# cc3d.net
KiCad netlist of a schematic drawn in Altium Designer
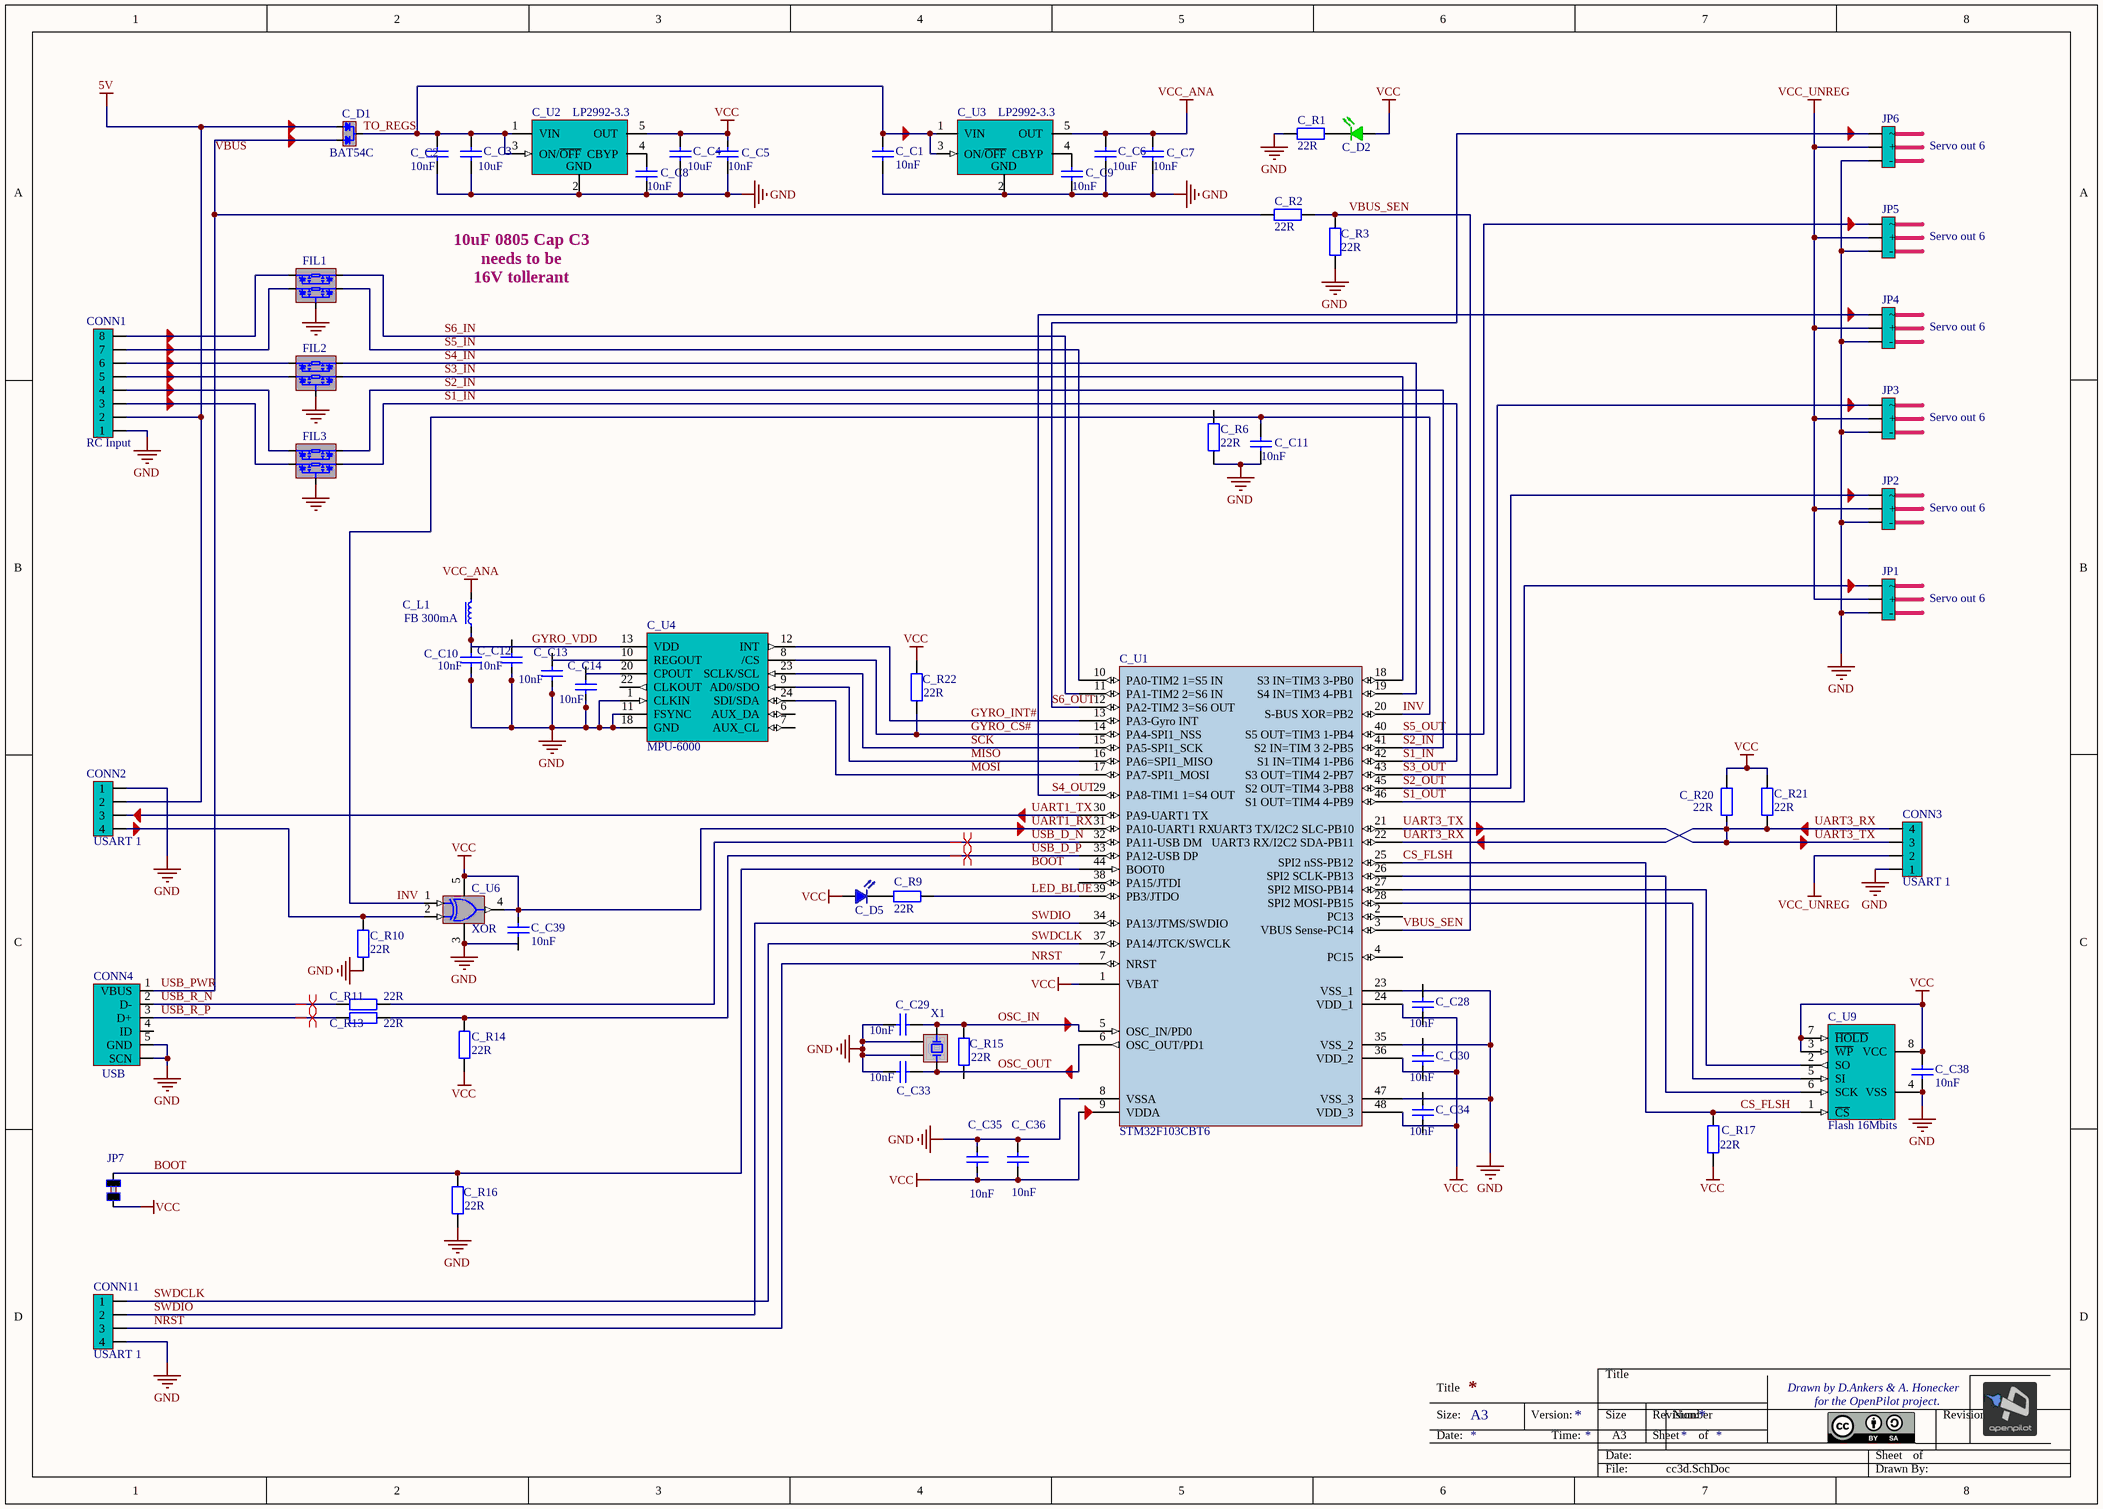
[diagram p0: cc3d.SchDoc]

(export (version "E")
  (design (tool "Eeschema 10.0.6"))
  (components
    (comp (ref "CONN1")
      (value "RC Input")
      (footprint "JST SH 8 Pin Side Entry")
      (description "JST-SH 8-pin Side Entry Socket")
      (fields (field (name "MANUFACTURER") "Generic Components"))
      (libsource (lib "CopterControl 3D") (part "JST-SH 8-pin Side Entry Socket"))
    )
    (comp (ref "CONN2")
      (value "USART 1")
      (footprint "JST SH 4 Pin Side Entry")
      (description "JST-SH 4-pin Side Entry Socket")
      (fields (field (name "MANUFACTURER") "Generic Components"))
      (libsource (lib "CopterControl 3D") (part "JST-SH 4-pin Side Entry Socket"))
    )
    (comp (ref "CONN3")
      (value "USART 1")
      (footprint "JST SH 4 Pin Side Entry")
      (description "JST-SH 4-pin Side Entry Socket")
      (fields (field (name "MANUFACTURER") "Generic Components"))
      (libsource (lib "") (part "JST-SH 4-pin Side Entry Socket_1"))
    )
    (comp (ref "CONN4")
      (value "USB")
      (footprint "USB SMD")
      (description "USB Type-B SMT Socket")
      (libsource (lib "CopterControl 3D") (part "USB_SMT_B"))
    )
    (comp (ref "CONN11")
      (value "USART 1")
      (footprint "JST SH 4 Pin Side Entry")
      (description "JST-SH 4-pin Side Entry Socket")
      (fields (field (name "MANUFACTURER") "Generic Components"))
      (libsource (lib "CopterControl 3D") (part "JST-SH 4-pin Side Entry Socket"))
    )
    (comp (ref "C_C1")
      (value "10nF")
      (footprint "CAP603N")
      (description "Capacitor SMD")
      (fields (field (name "Comment") "Cap603") (field (name "PUBLISHER") "The OpenPilot Project"))
      (libsource (lib "CopterControl 3D") (part "Cap603"))
    )
    (comp (ref "C_C2")
      (value "10nF")
      (footprint "CAP603L")
      (description "Capacitor SMD")
      (fields (field (name "Comment") "Cap603") (field (name "PUBLISHER") "The OpenPilot Project"))
      (libsource (lib "CopterControl 3D") (part "Cap603"))
    )
    (comp (ref "C_C3")
      (value "10uF")
      (footprint "CAP805L")
      (description "Capacitor SMD")
      (fields (field (name "Comment") "Cap805") (field (name "PUBLISHER") "The OpenPilot Project"))
      (libsource (lib "CopterControl 3D") (part "Cap805"))
    )
    (comp (ref "C_C4")
      (value "10uF")
      (footprint "CAP805L")
      (description "Capacitor SMD")
      (fields (field (name "Comment") "Cap805") (field (name "PUBLISHER") "The OpenPilot Project"))
      (libsource (lib "CopterControl 3D") (part "Cap805"))
    )
    (comp (ref "C_C5")
      (value "10nF")
      (footprint "CAP603N")
      (description "Capacitor SMD")
      (fields (field (name "Comment") "Cap603") (field (name "PUBLISHER") "The OpenPilot Project"))
      (libsource (lib "CopterControl 3D") (part "Cap603"))
    )
    (comp (ref "C_C6")
      (value "10uF")
      (footprint "CAP805L")
      (description "Capacitor SMD")
      (fields (field (name "Comment") "Cap805") (field (name "PUBLISHER") "The OpenPilot Project"))
      (libsource (lib "CopterControl 3D") (part "Cap805"))
    )
    (comp (ref "C_C7")
      (value "10nF")
      (footprint "CAP603N")
      (description "Capacitor SMD")
      (fields (field (name "Comment") "Cap603") (field (name "PUBLISHER") "The OpenPilot Project"))
      (libsource (lib "CopterControl 3D") (part "Cap603"))
    )
    (comp (ref "C_C8")
      (value "10nF")
      (footprint "CAP603N")
      (description "Capacitor SMD")
      (fields (field (name "Comment") "Cap603") (field (name "PUBLISHER") "The OpenPilot Project"))
      (libsource (lib "CopterControl 3D") (part "Cap603"))
    )
    (comp (ref "C_C9")
      (value "10nF")
      (footprint "CAP603N")
      (description "Capacitor SMD")
      (fields (field (name "Comment") "Cap603") (field (name "PUBLISHER") "The OpenPilot Project"))
      (libsource (lib "CopterControl 3D") (part "Cap603"))
    )
    (comp (ref "C_C10")
      (value "10nF")
      (footprint "CAP603L")
      (description "Capacitor SMD")
      (fields (field (name "Comment") "Cap603") (field (name "PUBLISHER") "The OpenPilot Project"))
      (libsource (lib "CopterControl 3D") (part "Cap603"))
    )
    (comp (ref "C_C11")
      (value "10nF")
      (footprint "CAP603N")
      (description "Capacitor SMD")
      (fields (field (name "Comment") "Cap603") (field (name "PUBLISHER") "The OpenPilot Project"))
      (libsource (lib "CopterControl 3D") (part "Cap603"))
    )
    (comp (ref "C_C12")
      (value "10nF")
      (footprint "CAP603L")
      (description "Capacitor SMD")
      (fields (field (name "Comment") "Cap603") (field (name "PUBLISHER") "The OpenPilot Project"))
      (libsource (lib "CopterControl 3D") (part "Cap603"))
    )
    (comp (ref "C_C13")
      (value "10nF")
      (footprint "CAP603L")
      (description "Capacitor SMD")
      (fields (field (name "Comment") "Cap603") (field (name "PUBLISHER") "The OpenPilot Project"))
      (libsource (lib "CopterControl 3D") (part "Cap603"))
    )
    (comp (ref "C_C14")
      (value "10nF")
      (footprint "CAP603L")
      (description "Capacitor SMD")
      (fields (field (name "Comment") "Cap603") (field (name "PUBLISHER") "The OpenPilot Project"))
      (libsource (lib "CopterControl 3D") (part "Cap603"))
    )
    (comp (ref "C_C28")
      (value "10nF")
      (footprint "CAP603N")
      (description "Capacitor SMD")
      (fields (field (name "Comment") "Cap603") (field (name "PUBLISHER") "The OpenPilot Project"))
      (libsource (lib "CopterControl 3D") (part "Cap603"))
    )
    (comp (ref "C_C29")
      (value "10nF")
      (footprint "CAP603N")
      (description "Capacitor SMD")
      (fields (field (name "Comment") "Cap603") (field (name "PUBLISHER") "The OpenPilot Project"))
      (libsource (lib "CopterControl 3D") (part "Cap603"))
    )
    (comp (ref "C_C30")
      (value "10nF")
      (footprint "CAP603N")
      (description "Capacitor SMD")
      (fields (field (name "Comment") "Cap603") (field (name "PUBLISHER") "The OpenPilot Project"))
      (libsource (lib "CopterControl 3D") (part "Cap603"))
    )
    (comp (ref "C_C33")
      (value "10nF")
      (footprint "CAP603N")
      (description "Capacitor SMD")
      (fields (field (name "Comment") "Cap603") (field (name "PUBLISHER") "The OpenPilot Project"))
      (libsource (lib "CopterControl 3D") (part "Cap603"))
    )
    (comp (ref "C_C34")
      (value "10nF")
      (footprint "CAP603N")
      (description "Capacitor SMD")
      (fields (field (name "Comment") "Cap603") (field (name "PUBLISHER") "The OpenPilot Project"))
      (libsource (lib "CopterControl 3D") (part "Cap603"))
    )
    (comp (ref "C_C35")
      (value "10nF")
      (footprint "CAP603L")
      (description "Capacitor SMD")
      (fields (field (name "Comment") "Cap603") (field (name "PUBLISHER") "The OpenPilot Project"))
      (libsource (lib "CopterControl 3D") (part "Cap603"))
    )
    (comp (ref "C_C36")
      (value "10nF")
      (footprint "CAP603N")
      (description "Capacitor SMD")
      (fields (field (name "Comment") "Cap603") (field (name "PUBLISHER") "The OpenPilot Project"))
      (libsource (lib "CopterControl 3D") (part "Cap603"))
    )
    (comp (ref "C_C38")
      (value "10nF")
      (footprint "CAP603N")
      (description "Capacitor SMD")
      (fields (field (name "Comment") "Cap603") (field (name "PUBLISHER") "The OpenPilot Project"))
      (libsource (lib "CopterControl 3D") (part "Cap603"))
    )
    (comp (ref "C_C39")
      (value "10nF")
      (footprint "CAP603N")
      (description "Capacitor SMD")
      (fields (field (name "Comment") "Cap603") (field (name "PUBLISHER") "The OpenPilot Project"))
      (libsource (lib "CopterControl 3D") (part "Cap603"))
    )
    (comp (ref "C_D1")
      (value "BAT54C")
      (footprint "SOT23-3N")
      (description "Dual Diode Command Cathode")
      (libsource (lib "CopterControl 3D") (part "BAT54C"))
    )
    (comp (ref "C_D2")
      (value "Green")
      (footprint "LED603N")
      (description "Green 603 LED")
      (libsource (lib "CopterControl 3D") (part "LED 603 Gr"))
    )
    (comp (ref "C_D5")
      (value "Blue")
      (footprint "LED603N")
      (description "Blue 603 LED")
      (libsource (lib "CopterControl 3D") (part "LED 603 Bl"))
    )
    (comp (ref "C_L1")
      (value "FB 300mA")
      (footprint "IND603N")
      (description "Ferrite Bead 300mA")
      (fields (field (name "MANUFACTURER") "Generic Components"))
      (libsource (lib "CopterControl 3D") (part "FerriteBead_300mA"))
    )
    (comp (ref "C_R1")
      (value "22R")
      (footprint "RES603N")
      (description "Resistor SMD")
      (fields (field (name "Comment") "Res603") (field (name "PUBLISHER") "The OpenPilot Project"))
      (libsource (lib "CopterControl 3D") (part "Res603"))
    )
    (comp (ref "C_R2")
      (value "22R")
      (footprint "RES603N")
      (description "Resistor SMD")
      (fields (field (name "Comment") "Res603") (field (name "PUBLISHER") "The OpenPilot Project"))
      (libsource (lib "CopterControl 3D") (part "Res603"))
    )
    (comp (ref "C_R3")
      (value "22R")
      (footprint "RES603N")
      (description "Resistor SMD")
      (fields (field (name "Comment") "Res603") (field (name "PUBLISHER") "The OpenPilot Project"))
      (libsource (lib "") (part "Res603_1"))
    )
    (comp (ref "C_R6")
      (value "22R")
      (footprint "RES603N")
      (description "Resistor SMD")
      (fields (field (name "Comment") "Res603") (field (name "PUBLISHER") "The OpenPilot Project"))
      (libsource (lib "") (part "Res603_1"))
    )
    (comp (ref "C_R9")
      (value "22R")
      (footprint "RES603N")
      (description "Resistor SMD")
      (fields (field (name "Comment") "Res603") (field (name "PUBLISHER") "The OpenPilot Project"))
      (libsource (lib "CopterControl 3D") (part "Res603"))
    )
    (comp (ref "C_R10")
      (value "22R")
      (footprint "RES603N")
      (description "Resistor SMD")
      (fields (field (name "Comment") "Res603") (field (name "PUBLISHER") "The OpenPilot Project"))
      (libsource (lib "") (part "Res603_1"))
    )
    (comp (ref "C_R11")
      (value "22R")
      (footprint "RES603N")
      (description "Resistor SMD")
      (fields (field (name "Comment") "Res603") (field (name "PUBLISHER") "The OpenPilot Project"))
      (libsource (lib "") (part "Res603_2"))
    )
    (comp (ref "C_R13")
      (value "22R")
      (footprint "RES603N")
      (description "Resistor SMD")
      (fields (field (name "Comment") "Res603") (field (name "PUBLISHER") "The OpenPilot Project"))
      (libsource (lib "") (part "Res603_2"))
    )
    (comp (ref "C_R14")
      (value "22R")
      (footprint "RES603N")
      (description "Resistor SMD")
      (fields (field (name "Comment") "Res603") (field (name "PUBLISHER") "The OpenPilot Project"))
      (libsource (lib "") (part "Res603_1"))
    )
    (comp (ref "C_R15")
      (value "22R")
      (footprint "RES603N")
      (description "Resistor SMD")
      (fields (field (name "Comment") "Res603") (field (name "PUBLISHER") "The OpenPilot Project"))
      (libsource (lib "") (part "Res603_1"))
    )
    (comp (ref "C_R16")
      (value "22R")
      (footprint "RES603N")
      (description "Resistor SMD")
      (fields (field (name "Comment") "Res603") (field (name "PUBLISHER") "The OpenPilot Project"))
      (libsource (lib "") (part "Res603_1"))
    )
    (comp (ref "C_R17")
      (value "22R")
      (footprint "RES603N")
      (description "Resistor SMD")
      (fields (field (name "Comment") "Res603") (field (name "PUBLISHER") "The OpenPilot Project"))
      (libsource (lib "") (part "Res603_1"))
    )
    (comp (ref "C_R20")
      (value "22R")
      (footprint "RES603N")
      (description "Resistor SMD")
      (fields (field (name "Comment") "Res603") (field (name "PUBLISHER") "The OpenPilot Project"))
      (libsource (lib "") (part "Res603_1"))
    )
    (comp (ref "C_R21")
      (value "22R")
      (footprint "RES603N")
      (description "Resistor SMD")
      (fields (field (name "Comment") "Res603") (field (name "PUBLISHER") "The OpenPilot Project"))
      (libsource (lib "") (part "Res603_1"))
    )
    (comp (ref "C_R22")
      (value "22R")
      (footprint "RES603N")
      (description "Resistor SMD")
      (fields (field (name "Comment") "Res603") (field (name "PUBLISHER") "The OpenPilot Project"))
      (libsource (lib "") (part "Res603_1"))
    )
    (comp (ref "C_U1")
      (value "STM32F103CBT6")
      (footprint "STM32 48 Lead")
      (description "STM32 ARM-based 32-bit MCU with 128 Kbytes Flash, 48-pin LQFP, Industrial Temperature")
      (fields (field (name "PUBLISHER") "Altium Limited"))
      (libsource (lib "CopterControl 3D") (part "STM32F103CBT6"))
    )
    (comp (ref "C_U2")
      (value "LP2992-3.3")
      (footprint "SOT23-5L")
      (description "3.3V 250mA LDO Regulator")
      (fields
        (field (name "MANUFACTURER") "National Semiconductor")
        (field (name "MANUFACTURER PART NUMBER") "LP2992AIM5-3.3/NOPB")
      )
      (libsource (lib "CopterControl 3D") (part "LP2985-3.3"))
    )
    (comp (ref "C_U3")
      (value "LP2992-3.3")
      (footprint "SOT23-5L")
      (description "3.3V 250mA LDO Regulator")
      (fields
        (field (name "MANUFACTURER") "National Semiconductor")
        (field (name "MANUFACTURER PART NUMBER") "LP2992AIM5-3.3/NOPB")
      )
      (libsource (lib "CopterControl 3D") (part "LP2985-3.3"))
    )
    (comp (ref "C_U4")
      (value "MPU-6000")
      (footprint "IMU-3000")
      (description "Invensense MPU-3/6000,  3-axis Gyros & Accel on 6000")
      (fields (field (name "MANUFACTURER") "Invensense") (field (name "PUBLISHER") "The OpenPilot Project"))
      (libsource (lib "CopterControl 3D") (part "MPU-3/6000"))
    )
    (comp (ref "C_U6")
      (value "XOR")
      (footprint "DCK-5")
      (description "XOR Gate SN74LVC1G86DCKR")
      (libsource (lib "CopterControl 3D") (part "XOR SN74LVC1G86DCKR"))
    )
    (comp (ref "C_U9")
      (value "Flash 16Mbits")
      (footprint "SOIC8_N")
      (description "16Mbit SPI Flash Memory")
      (fields (field (name "PUBLISHER") "The OpenPilot Project"))
      (libsource (lib "CopterControl 3D") (part "Flash 16Mb 75MHZ 8SOIC"))
    )
    (comp (ref "FIL1")
      (value "IP4256CZ5-W,115")
      (footprint "SOT-665")
      (description "IP4256CZ5-W,115 2 channel, 100R, 30pF, RF ESD Filter")
      (fields
        (field (name "MANUFACTURER") "Generic Components")
        (field (name "PUBLISHER") "The OpenPilot Project")
      )
      (libsource (lib "CopterControl 3D") (part "RF Filter 100R 30pF"))
    )
    (comp (ref "FIL2")
      (value "IP4256CZ5-W,115")
      (footprint "SOT-665")
      (description "IP4256CZ5-W,115 2 channel, 100R, 30pF, RF ESD Filter")
      (fields
        (field (name "MANUFACTURER") "Generic Components")
        (field (name "PUBLISHER") "The OpenPilot Project")
      )
      (libsource (lib "CopterControl 3D") (part "RF Filter 100R 30pF"))
    )
    (comp (ref "FIL3")
      (value "IP4256CZ5-W,115")
      (footprint "SOT-665")
      (description "IP4256CZ5-W,115 2 channel, 100R, 30pF, RF ESD Filter")
      (fields
        (field (name "MANUFACTURER") "Generic Components")
        (field (name "PUBLISHER") "The OpenPilot Project")
      )
      (libsource (lib "CopterControl 3D") (part "RF Filter 100R 30pF"))
    )
    (comp (ref "JP1")
      (value "Servo out 6")
      (footprint "SIP3 - 0.1")
      (description "Header, 3-Pin, 0.1\"")
      (fields (field (name "MANUFACTURER") "Generic Components"))
      (libsource (lib "CopterControl 3D") (part "Hdr 3 Pin 0.1"))
    )
    (comp (ref "JP2")
      (value "Servo out 6")
      (footprint "SIP3 - 0.1")
      (description "Header, 3-Pin, 0.1\"")
      (fields (field (name "MANUFACTURER") "Generic Components"))
      (libsource (lib "CopterControl 3D") (part "Hdr 3 Pin 0.1"))
    )
    (comp (ref "JP3")
      (value "Servo out 6")
      (footprint "SIP3 - 0.1")
      (description "Header, 3-Pin, 0.1\"")
      (fields (field (name "MANUFACTURER") "Generic Components"))
      (libsource (lib "CopterControl 3D") (part "Hdr 3 Pin 0.1"))
    )
    (comp (ref "JP4")
      (value "Servo out 6")
      (footprint "SIP3 - 0.1")
      (description "Header, 3-Pin, 0.1\"")
      (fields (field (name "MANUFACTURER") "Generic Components"))
      (libsource (lib "CopterControl 3D") (part "Hdr 3 Pin 0.1"))
    )
    (comp (ref "JP5")
      (value "Servo out 6")
      (footprint "SIP3 - 0.1")
      (description "Header, 3-Pin, 0.1\"")
      (fields (field (name "MANUFACTURER") "Generic Components"))
      (libsource (lib "CopterControl 3D") (part "Hdr 3 Pin 0.1"))
    )
    (comp (ref "JP6")
      (value "Servo out 6")
      (footprint "SIP3 - 0.1")
      (description "Header, 3-Pin, 0.1\"")
      (fields (field (name "MANUFACTURER") "Generic Components"))
      (libsource (lib "CopterControl 3D") (part "Hdr 3 Pin 0.1"))
    )
    (comp (ref "JP7")
      (value "2 PAD Touch JMP")
      (footprint "TOUCH JMP 2PAD")
      (description "2 Pad Touch Jumper")
      (fields (field (name "PUBLISHER") "The OpenPilot Project"))
      (libsource (lib "CopterControl 3D") (part "2 PAD Touch JMP"))
    )
    (comp (ref "X1")
      (value "8MHz")
      (footprint "XTAL ACT530SMX-4 Series")
      (description "Surface Mount Quartz Crystal, Digikey 535-9720-1-ND")
      (libsource (lib "CopterControl 3D") (part "XTAL ACT530SMX-4"))
    )
  )
  (nets
    (net (code "1") (name "/BOOT") (class "Default")
      (node (ref "C_R16") (pin "2") (pinfunction "2_2") (pintype "passive"))
      (node (ref "C_U1") (pin "44") (pinfunction "BOOT0_44") (pintype "input"))
      (node (ref "JP7") (pin "1") (pinfunction "1_1") (pintype "passive"))
    )
    (net (code "2") (name "/CS_FLSH") (class "Default")
      (node (ref "C_R17") (pin "2") (pinfunction "2_2") (pintype "passive"))
      (node (ref "C_U1") (pin "25") (pinfunction "SPI2_nSS-PB12_25") (pintype "bidirectional"))
      (node (ref "C_U9") (pin "1") (pinfunction "~{CS}_1") (pintype "input"))
    )
    (net (code "3") (name "/GYRO_CS#") (class "Default")
      (node (ref "C_R22") (pin "1") (pinfunction "1_1") (pintype "passive"))
      (node (ref "C_U1") (pin "14") (pinfunction "PA4-SPI1_NSS_14") (pintype "bidirectional"))
      (node (ref "C_U4") (pin "8") (pinfunction "/CS_8") (pintype "passive"))
    )
    (net (code "4") (name "/GYRO_INT#") (class "Default")
      (node (ref "C_U1") (pin "13") (pinfunction "PA3-Gyro_INT_13") (pintype "bidirectional"))
      (node (ref "C_U4") (pin "12") (pinfunction "INT_12") (pintype "output"))
    )
    (net (code "5") (name "/GYRO_VDD") (class "Default")
      (node (ref "C_C10") (pin "1") (pinfunction "1_1") (pintype "passive"))
      (node (ref "C_L1") (pin "1") (pinfunction "1_1") (pintype "passive"))
      (node (ref "C_U4") (pin "13") (pinfunction "VDD_13") (pintype "power_in"))
    )
    (net (code "6") (name "/INV") (class "Default")
      (node (ref "C_C11") (pin "1") (pinfunction "1_1") (pintype "passive"))
      (node (ref "C_U1") (pin "20") (pinfunction "S-BUS_XOR=PB2_20") (pintype "bidirectional"))
      (node (ref "C_U6") (pin "1") (pinfunction "A_1") (pintype "input"))
    )
    (net (code "7") (name "/LED_BLUE") (class "Default")
      (node (ref "C_R9") (pin "2") (pinfunction "2_2") (pintype "passive"))
      (node (ref "C_U1") (pin "39") (pinfunction "PB3/JTDO_39") (pintype "bidirectional"))
    )
    (net (code "8") (name "/MISO") (class "Default")
      (node (ref "C_U1") (pin "16") (pinfunction "PA6=SPI1_MISO_16") (pintype "bidirectional"))
      (node (ref "C_U4") (pin "9") (pinfunction "AD0/SDO_9") (pintype "input"))
    )
    (net (code "9") (name "/MOSI") (class "Default")
      (node (ref "C_U1") (pin "17") (pinfunction "PA7-SPI1_MOSI_17") (pintype "bidirectional"))
      (node (ref "C_U4") (pin "24") (pinfunction "SDI/SDA_24") (pintype "bidirectional"))
    )
    (net (code "10") (name "/NRST") (class "Default")
      (node (ref "CONN11") (pin "3") (pinfunction "3_3") (pintype "passive"))
      (node (ref "C_U1") (pin "7") (pinfunction "NRST_7") (pintype "bidirectional"))
    )
    (net (code "11") (name "/OSC_IN") (class "Default")
      (node (ref "C_C29") (pin "2") (pinfunction "2_2") (pintype "passive"))
      (node (ref "C_R15") (pin "2") (pinfunction "2_2") (pintype "passive"))
      (node (ref "C_U1") (pin "5") (pinfunction "OSC_IN/PD0_5") (pintype "input"))
      (node (ref "X1") (pin "3") (pinfunction "3_3") (pintype "passive"))
    )
    (net (code "12") (name "/OSC_OUT") (class "Default")
      (node (ref "C_C33") (pin "2") (pinfunction "2_2") (pintype "passive"))
      (node (ref "C_U1") (pin "6") (pinfunction "OSC_OUT/PD1_6") (pintype "output"))
      (node (ref "X1") (pin "1") (pinfunction "1_1") (pintype "passive"))
    )
    (net (code "13") (name "/S1_IN") (class "Default")
      (node (ref "C_U1") (pin "42") (pinfunction "S1_IN=TIM4_1-PB6_42") (pintype "bidirectional"))
      (node (ref "FIL3") (pin "5") (pinfunction "5_5") (pintype "passive"))
    )
    (net (code "14") (name "/S1_OUT") (class "Default")
      (node (ref "C_U1") (pin "46") (pinfunction "S1_OUT=TIM4_4-PB9_46") (pintype "bidirectional"))
      (node (ref "JP1") (pin "1") (pinfunction "~_1") (pintype "passive"))
    )
    (net (code "15") (name "/S2_IN") (class "Default")
      (node (ref "C_U1") (pin "41") (pinfunction "S2_IN=TIM_3_2-PB5_41") (pintype "bidirectional"))
      (node (ref "FIL3") (pin "4") (pinfunction "4_4") (pintype "passive"))
    )
    (net (code "16") (name "/S2_OUT") (class "Default")
      (node (ref "C_U1") (pin "45") (pinfunction "S2_OUT=TIM4_3-PB8_45") (pintype "bidirectional"))
      (node (ref "JP2") (pin "1") (pinfunction "~_1") (pintype "passive"))
    )
    (net (code "17") (name "/S3_IN") (class "Default")
      (node (ref "C_U1") (pin "18") (pinfunction "S3_IN=TIM3_3-PB0_18") (pintype "bidirectional"))
      (node (ref "FIL2") (pin "5") (pinfunction "5_5") (pintype "passive"))
    )
    (net (code "18") (name "/S3_OUT") (class "Default")
      (node (ref "C_U1") (pin "43") (pinfunction "S3_OUT=TIM4_2-PB7_43") (pintype "bidirectional"))
      (node (ref "JP3") (pin "1") (pinfunction "~_1") (pintype "passive"))
    )
    (net (code "19") (name "/S4_IN") (class "Default")
      (node (ref "C_U1") (pin "19") (pinfunction "S4_IN=TIM3_4-PB1_19") (pintype "bidirectional"))
      (node (ref "FIL2") (pin "4") (pinfunction "4_4") (pintype "passive"))
    )
    (net (code "20") (name "/S4_OUT") (class "Default")
      (node (ref "C_U1") (pin "29") (pinfunction "PA8-TIM1_1=S4_OUT_29") (pintype "bidirectional"))
      (node (ref "JP4") (pin "1") (pinfunction "~_1") (pintype "passive"))
    )
    (net (code "21") (name "/S5_IN") (class "Default")
      (node (ref "C_U1") (pin "10") (pinfunction "PA0-TIM2_1=S5_IN_10") (pintype "bidirectional"))
      (node (ref "FIL1") (pin "5") (pinfunction "5_5") (pintype "passive"))
    )
    (net (code "22") (name "/S5_OUT") (class "Default")
      (node (ref "C_U1") (pin "40") (pinfunction "S5_OUT=TIM3_1-PB4_40") (pintype "bidirectional"))
      (node (ref "JP5") (pin "1") (pinfunction "~_1") (pintype "passive"))
    )
    (net (code "23") (name "/S6_IN") (class "Default")
      (node (ref "C_U1") (pin "11") (pinfunction "PA1-TIM2_2=S6_IN_11") (pintype "bidirectional"))
      (node (ref "FIL1") (pin "4") (pinfunction "4_4") (pintype "passive"))
    )
    (net (code "24") (name "/S6_OUT") (class "Default")
      (node (ref "C_U1") (pin "12") (pinfunction "PA2-TIM2_3=S6_OUT_12") (pintype "bidirectional"))
      (node (ref "JP6") (pin "1") (pinfunction "~_1") (pintype "passive"))
    )
    (net (code "25") (name "/SCK") (class "Default")
      (node (ref "C_U1") (pin "15") (pinfunction "PA5-SPI1_SCK_15") (pintype "bidirectional"))
      (node (ref "C_U4") (pin "23") (pinfunction "SCLK/SCL_23") (pintype "input"))
    )
    (net (code "26") (name "/SWDCLK") (class "Default")
      (node (ref "CONN11") (pin "1") (pinfunction "1_1") (pintype "passive"))
      (node (ref "C_U1") (pin "37") (pinfunction "PA14/JTCK/SWCLK_37") (pintype "bidirectional"))
    )
    (net (code "27") (name "/SWDIO") (class "Default")
      (node (ref "CONN11") (pin "2") (pinfunction "2_2") (pintype "passive"))
      (node (ref "C_U1") (pin "34") (pinfunction "PA13/JTMS/SWDIO_34") (pintype "bidirectional"))
    )
    (net (code "28") (name "/TO_REGS") (class "Default")
      (node (ref "C_C1") (pin "1") (pinfunction "1_1") (pintype "passive"))
      (node (ref "C_C2") (pin "1") (pinfunction "1_1") (pintype "passive"))
      (node (ref "C_C3") (pin "1") (pinfunction "1_1") (pintype "passive"))
      (node (ref "C_D1") (pin "3") (pinfunction "COM_3") (pintype "passive"))
      (node (ref "C_U2") (pin "1") (pinfunction "VIN_1") (pintype "power_in"))
      (node (ref "C_U2") (pin "3") (pinfunction "ON/~{OFF}_3") (pintype "input"))
      (node (ref "C_U3") (pin "1") (pinfunction "VIN_1") (pintype "power_in"))
      (node (ref "C_U3") (pin "3") (pinfunction "ON/~{OFF}_3") (pintype "input"))
    )
    (net (code "29") (name "/UART1_TX") (class "Default")
      (node (ref "CONN2") (pin "3") (pinfunction "3_3") (pintype "passive"))
      (node (ref "C_U1") (pin "30") (pinfunction "PA9-UART1_TX_30") (pintype "bidirectional"))
    )
    (net (code "30") (name "/UART3_RX") (class "Default")
      (node (ref "CONN3") (pin "3") (pinfunction "3_3") (pintype "passive"))
      (node (ref "CONN3") (pin "4") (pinfunction "4_4") (pintype "passive"))
      (node (ref "C_R20") (pin "1") (pinfunction "1_1") (pintype "passive"))
      (node (ref "C_R21") (pin "1") (pinfunction "1_1") (pintype "passive"))
      (node (ref "C_U1") (pin "21") (pinfunction "UART3_TX/I2C2_SLC-PB10_21") (pintype "bidirectional"))
      (node (ref "C_U1") (pin "22") (pinfunction "UART3_RX/I2C2_SDA-PB11_22") (pintype "bidirectional"))
    )
    (net (code "31") (name "/USB_D_N") (class "Default")
      (node (ref "C_R11") (pin "1") (pinfunction "1_1") (pintype "passive"))
      (node (ref "C_U1") (pin "32") (pinfunction "PA11-USB_DM_32") (pintype "bidirectional"))
    )
    (net (code "32") (name "/USB_D_P") (class "Default")
      (node (ref "C_R13") (pin "1") (pinfunction "1_1") (pintype "passive"))
      (node (ref "C_R14") (pin "2") (pinfunction "2_2") (pintype "passive"))
      (node (ref "C_U1") (pin "33") (pinfunction "PA12-USB_DP_33") (pintype "bidirectional"))
    )
    (net (code "33") (name "/USB_PWR") (class "Default")
      (node (ref "CONN4") (pin "1") (pinfunction "VBUS_1") (pintype "passive"))
      (node (ref "C_D1") (pin "1") (pinfunction "A1_1") (pintype "passive"))
      (node (ref "C_R2") (pin "1") (pinfunction "1_1") (pintype "passive"))
    )
    (net (code "34") (name "/USB_R_N") (class "Default")
      (node (ref "CONN4") (pin "2") (pinfunction "D-_2") (pintype "passive"))
      (node (ref "C_R11") (pin "2") (pinfunction "2_2") (pintype "passive"))
    )
    (net (code "35") (name "/USB_R_P") (class "Default")
      (node (ref "CONN4") (pin "3") (pinfunction "D+_3") (pintype "passive"))
      (node (ref "C_R13") (pin "2") (pinfunction "2_2") (pintype "passive"))
    )
    (net (code "36") (name "/VBUS_SEN") (class "Default")
      (node (ref "C_R2") (pin "2") (pinfunction "2_2") (pintype "passive"))
      (node (ref "C_R3") (pin "2") (pinfunction "2_2") (pintype "passive"))
      (node (ref "C_U1") (pin "3") (pinfunction "VBUS_Sense-PC14_3") (pintype "bidirectional"))
    )
    (net (code "37") (name "5V") (class "Default")
      (node (ref "CONN1") (pin "2") (pinfunction "2_2") (pintype "passive"))
      (node (ref "CONN2") (pin "2") (pinfunction "2_2") (pintype "passive"))
      (node (ref "C_D1") (pin "2") (pinfunction "A2_2") (pintype "passive"))
    )
    (net (code "38") (name "GND") (class "Default")
      (node (ref "CONN1") (pin "1") (pinfunction "1_1") (pintype "passive"))
      (node (ref "CONN11") (pin "4") (pinfunction "4_4") (pintype "passive"))
      (node (ref "CONN2") (pin "1") (pinfunction "1_1") (pintype "passive"))
      (node (ref "CONN3") (pin "1") (pinfunction "1_1") (pintype "passive"))
      (node (ref "CONN4") (pin "0") (pinfunction "SCN_0") (pintype "passive"))
      (node (ref "CONN4") (pin "5") (pinfunction "GND_5") (pintype "passive"))
      (node (ref "C_C1") (pin "2") (pinfunction "2_2") (pintype "passive"))
      (node (ref "C_C10") (pin "2") (pinfunction "2_2") (pintype "passive"))
      (node (ref "C_C11") (pin "2") (pinfunction "2_2") (pintype "passive"))
      (node (ref "C_C12") (pin "2") (pinfunction "2_2") (pintype "passive"))
      (node (ref "C_C13") (pin "2") (pinfunction "2_2") (pintype "passive"))
      (node (ref "C_C14") (pin "1") (pinfunction "1_1") (pintype "passive"))
      (node (ref "C_C2") (pin "2") (pinfunction "2_2") (pintype "passive"))
      (node (ref "C_C29") (pin "1") (pinfunction "1_1") (pintype "passive"))
      (node (ref "C_C3") (pin "2") (pinfunction "2_2") (pintype "passive"))
      (node (ref "C_C33") (pin "1") (pinfunction "1_1") (pintype "passive"))
      (node (ref "C_C35") (pin "2") (pinfunction "2_2") (pintype "passive"))
      (node (ref "C_C36") (pin "1") (pinfunction "1_1") (pintype "passive"))
      (node (ref "C_C38") (pin "2") (pinfunction "2_2") (pintype "passive"))
      (node (ref "C_C4") (pin "2") (pinfunction "2_2") (pintype "passive"))
      (node (ref "C_C5") (pin "2") (pinfunction "2_2") (pintype "passive"))
      (node (ref "C_C6") (pin "2") (pinfunction "2_2") (pintype "passive"))
      (node (ref "C_C7") (pin "2") (pinfunction "2_2") (pintype "passive"))
      (node (ref "C_C8") (pin "2") (pinfunction "2_2") (pintype "passive"))
      (node (ref "C_C9") (pin "2") (pinfunction "2_2") (pintype "passive"))
      (node (ref "C_R1") (pin "1") (pinfunction "1_1") (pintype "passive"))
      (node (ref "C_R10") (pin "1") (pinfunction "1_1") (pintype "passive"))
      (node (ref "C_R16") (pin "1") (pinfunction "1_1") (pintype "passive"))
      (node (ref "C_R3") (pin "1") (pinfunction "1_1") (pintype "passive"))
      (node (ref "C_R6") (pin "1") (pinfunction "1_1") (pintype "passive"))
      (node (ref "C_U1") (pin "23") (pinfunction "VSS_1_23") (pintype "power_in"))
      (node (ref "C_U1") (pin "35") (pinfunction "VSS_2_35") (pintype "power_in"))
      (node (ref "C_U1") (pin "47") (pinfunction "VSS_3_47") (pintype "power_in"))
      (node (ref "C_U1") (pin "8") (pinfunction "VSSA_8") (pintype "power_in"))
      (node (ref "C_U2") (pin "2") (pinfunction "GND_2") (pintype "power_in"))
      (node (ref "C_U3") (pin "2") (pinfunction "GND_2") (pintype "power_in"))
      (node (ref "C_U4") (pin "1") (pinfunction "CLKIN_1") (pintype "input"))
      (node (ref "C_U4") (pin "11") (pinfunction "FSYNC_11") (pintype "passive"))
      (node (ref "C_U4") (pin "18") (pinfunction "GND_18") (pintype "power_in"))
      (node (ref "C_U6") (pin "3") (pinfunction "GND_3") (pintype "power_in"))
      (node (ref "C_U9") (pin "4") (pinfunction "VSS_4") (pintype "power_in"))
      (node (ref "FIL1") (pin "2") (pinfunction "PAD_2") (pintype "passive"))
      (node (ref "FIL2") (pin "2") (pinfunction "PAD_2") (pintype "passive"))
      (node (ref "FIL3") (pin "2") (pinfunction "PAD_2") (pintype "passive"))
      (node (ref "JP1") (pin "3") (pinfunction "-_3") (pintype "passive"))
      (node (ref "JP2") (pin "3") (pinfunction "-_3") (pintype "passive"))
      (node (ref "JP3") (pin "3") (pinfunction "-_3") (pintype "passive"))
      (node (ref "JP4") (pin "3") (pinfunction "-_3") (pintype "passive"))
      (node (ref "JP5") (pin "3") (pinfunction "-_3") (pintype "passive"))
      (node (ref "JP6") (pin "3") (pinfunction "-_3") (pintype "passive"))
      (node (ref "X1") (pin "2") (pinfunction "2_2") (pintype "passive"))
      (node (ref "X1") (pin "4") (pinfunction "4_4") (pintype "passive"))
    )
    (net (code "39") (name "Net-(CONN1-Pad3)") (class "Default")
      (node (ref "CONN1") (pin "3") (pinfunction "3_3") (pintype "passive"))
      (node (ref "FIL3") (pin "1") (pinfunction "1_1") (pintype "passive"))
    )
    (net (code "40") (name "Net-(CONN1-Pad4)") (class "Default")
      (node (ref "CONN1") (pin "4") (pinfunction "4_4") (pintype "passive"))
      (node (ref "FIL3") (pin "3") (pinfunction "3_3") (pintype "passive"))
    )
    (net (code "41") (name "Net-(CONN1-Pad5)") (class "Default")
      (node (ref "CONN1") (pin "5") (pinfunction "5_5") (pintype "passive"))
      (node (ref "FIL2") (pin "1") (pinfunction "1_1") (pintype "passive"))
    )
    (net (code "42") (name "Net-(CONN1-Pad6)") (class "Default")
      (node (ref "CONN1") (pin "6") (pinfunction "6_6") (pintype "passive"))
      (node (ref "FIL2") (pin "3") (pinfunction "3_3") (pintype "passive"))
    )
    (net (code "43") (name "Net-(CONN1-Pad7)") (class "Default")
      (node (ref "CONN1") (pin "7") (pinfunction "7_7") (pintype "passive"))
      (node (ref "FIL1") (pin "1") (pinfunction "1_1") (pintype "passive"))
    )
    (net (code "44") (name "Net-(CONN1-Pad8)") (class "Default")
      (node (ref "CONN1") (pin "8") (pinfunction "8_8") (pintype "passive"))
      (node (ref "FIL1") (pin "3") (pinfunction "3_3") (pintype "passive"))
    )
    (net (code "45") (name "Net-(C_D2-K)") (class "Default")
      (node (ref "C_D2") (pin "1") (pinfunction "K_1") (pintype "passive"))
      (node (ref "C_R1") (pin "2") (pinfunction "2_2") (pintype "passive"))
    )
    (net (code "46") (name "Net-(C_D5-K)") (class "Default")
      (node (ref "C_D5") (pin "1") (pinfunction "K_1") (pintype "passive"))
      (node (ref "C_R9") (pin "1") (pinfunction "1_1") (pintype "passive"))
    )
    (net (code "47") (name "Net-(C_U1-SPI2_MISO-PB14)") (class "Default")
      (node (ref "C_U1") (pin "27") (pinfunction "SPI2_MISO-PB14_27") (pintype "bidirectional"))
      (node (ref "C_U9") (pin "2") (pinfunction "SO_2") (pintype "output"))
    )
    (net (code "48") (name "Net-(C_U1-SPI2_MOSI-PB15)") (class "Default")
      (node (ref "C_U1") (pin "28") (pinfunction "SPI2_MOSI-PB15_28") (pintype "bidirectional"))
      (node (ref "C_U9") (pin "5") (pinfunction "SI_5") (pintype "input"))
    )
    (net (code "49") (name "Net-(C_U1-SPI2_SCLK-PB13)") (class "Default")
      (node (ref "C_U1") (pin "26") (pinfunction "SPI2_SCLK-PB13_26") (pintype "bidirectional"))
      (node (ref "C_U9") (pin "6") (pinfunction "SCK_6") (pintype "input"))
    )
    (net (code "50") (name "Net-(C_U2-CBYP)") (class "Default")
      (node (ref "C_C8") (pin "1") (pinfunction "1_1") (pintype "passive"))
      (node (ref "C_U2") (pin "4") (pinfunction "CBYP_4") (pintype "passive"))
    )
    (net (code "51") (name "Net-(C_U3-CBYP)") (class "Default")
      (node (ref "C_C9") (pin "1") (pinfunction "1_1") (pintype "passive"))
      (node (ref "C_U3") (pin "4") (pinfunction "CBYP_4") (pintype "passive"))
    )
    (net (code "52") (name "Net-(C_U6-B)") (class "Default")
      (node (ref "CONN2") (pin "4") (pinfunction "4_4") (pintype "passive"))
      (node (ref "C_R10") (pin "2") (pinfunction "2_2") (pintype "passive"))
      (node (ref "C_U6") (pin "2") (pinfunction "B_2") (pintype "input"))
    )
    (net (code "53") (name "VCC") (class "Default")
      (node (ref "C_C35") (pin "1") (pinfunction "1_1") (pintype "passive"))
      (node (ref "C_C36") (pin "2") (pinfunction "2_2") (pintype "passive"))
      (node (ref "C_C38") (pin "1") (pinfunction "1_1") (pintype "passive"))
      (node (ref "C_C39") (pin "1") (pinfunction "1_1") (pintype "passive"))
      (node (ref "C_C4") (pin "1") (pinfunction "1_1") (pintype "passive"))
      (node (ref "C_C5") (pin "1") (pinfunction "1_1") (pintype "passive"))
      (node (ref "C_D2") (pin "2") (pinfunction "A_2") (pintype "passive"))
      (node (ref "C_D5") (pin "2") (pinfunction "A_2") (pintype "passive"))
      (node (ref "C_R14") (pin "1") (pinfunction "1_1") (pintype "passive"))
      (node (ref "C_R17") (pin "1") (pinfunction "1_1") (pintype "passive"))
      (node (ref "C_R20") (pin "2") (pinfunction "2_2") (pintype "passive"))
      (node (ref "C_R21") (pin "2") (pinfunction "2_2") (pintype "passive"))
      (node (ref "C_R22") (pin "2") (pinfunction "2_2") (pintype "passive"))
      (node (ref "C_U1") (pin "1") (pinfunction "VBAT_1") (pintype "power_in"))
      (node (ref "C_U1") (pin "24") (pinfunction "VDD_1_24") (pintype "power_in"))
      (node (ref "C_U1") (pin "31") (pinfunction "PA10-UART1_RX_31") (pintype "bidirectional"))
      (node (ref "C_U1") (pin "36") (pinfunction "VDD_2_36") (pintype "power_in"))
      (node (ref "C_U1") (pin "48") (pinfunction "VDD_3_48") (pintype "power_in"))
      (node (ref "C_U1") (pin "9") (pinfunction "VDDA_9") (pintype "power_in"))
      (node (ref "C_U2") (pin "5") (pinfunction "OUT_5") (pintype "power_in"))
      (node (ref "C_U6") (pin "4") (pinfunction "Y_4") (pintype "output"))
      (node (ref "C_U6") (pin "5") (pinfunction "VCC_5") (pintype "power_in"))
      (node (ref "C_U9") (pin "3") (pinfunction "~{WP}_3") (pintype "input"))
      (node (ref "C_U9") (pin "7") (pinfunction "~{HOLD}_7") (pintype "input"))
      (node (ref "C_U9") (pin "8") (pinfunction "VCC_8") (pintype "power_in"))
      (node (ref "JP7") (pin "2") (pinfunction "2_2") (pintype "passive"))
    )
    (net (code "54") (name "VCC_ANA") (class "Default")
      (node (ref "C_C6") (pin "1") (pinfunction "1_1") (pintype "passive"))
      (node (ref "C_C7") (pin "1") (pinfunction "1_1") (pintype "passive"))
      (node (ref "C_L1") (pin "2") (pinfunction "2_2") (pintype "passive"))
      (node (ref "C_U3") (pin "5") (pinfunction "OUT_5") (pintype "power_in"))
    )
    (net (code "55") (name "VCC_UNREG") (class "Default")
      (node (ref "CONN3") (pin "2") (pinfunction "2_2") (pintype "passive"))
      (node (ref "JP1") (pin "2") (pinfunction "+_2") (pintype "passive"))
      (node (ref "JP2") (pin "2") (pinfunction "+_2") (pintype "passive"))
      (node (ref "JP3") (pin "2") (pinfunction "+_2") (pintype "passive"))
      (node (ref "JP4") (pin "2") (pinfunction "+_2") (pintype "passive"))
      (node (ref "JP5") (pin "2") (pinfunction "+_2") (pintype "passive"))
      (node (ref "JP6") (pin "2") (pinfunction "+_2") (pintype "passive"))
    )
    (net (code "56") (name "unconnected-(CONN4-ID-Pad4)") (class "Default")
      (node (ref "CONN4") (pin "4") (pinfunction "ID_4") (pintype "passive"))
    )
    (net (code "57") (name "unconnected-(C_C12-Pad1)") (class "Default")
      (node (ref "C_C12") (pin "1") (pinfunction "1_1") (pintype "passive"))
    )
    (net (code "58") (name "unconnected-(C_C13-Pad1)") (class "Default")
      (node (ref "C_C13") (pin "1") (pinfunction "1_1") (pintype "passive"))
    )
    (net (code "59") (name "unconnected-(C_C14-Pad2)") (class "Default")
      (node (ref "C_C14") (pin "2") (pinfunction "2_2") (pintype "passive"))
    )
    (net (code "60") (name "unconnected-(C_C28-Pad1)") (class "Default")
      (node (ref "C_C28") (pin "1") (pinfunction "1_1") (pintype "passive"))
    )
    (net (code "61") (name "unconnected-(C_C28-Pad2)") (class "Default")
      (node (ref "C_C28") (pin "2") (pinfunction "2_2") (pintype "passive"))
    )
    (net (code "62") (name "unconnected-(C_C30-Pad1)") (class "Default")
      (node (ref "C_C30") (pin "1") (pinfunction "1_1") (pintype "passive"))
    )
    (net (code "63") (name "unconnected-(C_C30-Pad2)") (class "Default")
      (node (ref "C_C30") (pin "2") (pinfunction "2_2") (pintype "passive"))
    )
    (net (code "64") (name "unconnected-(C_C34-Pad1)") (class "Default")
      (node (ref "C_C34") (pin "1") (pinfunction "1_1") (pintype "passive"))
    )
    (net (code "65") (name "unconnected-(C_C34-Pad2)") (class "Default")
      (node (ref "C_C34") (pin "2") (pinfunction "2_2") (pintype "passive"))
    )
    (net (code "66") (name "unconnected-(C_C39-Pad2)") (class "Default")
      (node (ref "C_C39") (pin "2") (pinfunction "2_2") (pintype "passive"))
    )
    (net (code "67") (name "unconnected-(C_R6-Pad2)") (class "Default")
      (node (ref "C_R6") (pin "2") (pinfunction "2_2") (pintype "passive"))
    )
    (net (code "68") (name "unconnected-(C_R15-Pad1)") (class "Default")
      (node (ref "C_R15") (pin "1") (pinfunction "1_1") (pintype "passive"))
    )
    (net (code "69") (name "unconnected-(C_U1-PA15{slash}JTDI-Pad38)") (class "Default")
      (node (ref "C_U1") (pin "38") (pinfunction "PA15/JTDI_38") (pintype "bidirectional"))
    )
    (net (code "70") (name "unconnected-(C_U1-PC13-Pad2)") (class "Default")
      (node (ref "C_U1") (pin "2") (pinfunction "PC13_2") (pintype "bidirectional"))
    )
    (net (code "71") (name "unconnected-(C_U1-PC15-Pad4)") (class "Default")
      (node (ref "C_U1") (pin "4") (pinfunction "PC15_4") (pintype "bidirectional"))
    )
    (net (code "72") (name "unconnected-(C_U4-AUX_CL-Pad7)") (class "Default")
      (node (ref "C_U4") (pin "7") (pinfunction "AUX_CL_7") (pintype "bidirectional"))
    )
    (net (code "73") (name "unconnected-(C_U4-AUX_DA-Pad6)") (class "Default")
      (node (ref "C_U4") (pin "6") (pinfunction "AUX_DA_6") (pintype "bidirectional"))
    )
    (net (code "74") (name "unconnected-(C_U4-CLKOUT-Pad22)") (class "Default")
      (node (ref "C_U4") (pin "22") (pinfunction "CLKOUT_22") (pintype "output"))
    )
    (net (code "75") (name "unconnected-(C_U4-CPOUT-Pad20)") (class "Default")
      (node (ref "C_U4") (pin "20") (pinfunction "CPOUT_20") (pintype "passive"))
    )
    (net (code "76") (name "unconnected-(C_U4-NC-Pad2)") (class "Default")
      (node (ref "C_U4") (pin "2") (pinfunction "NC_2") (pintype "tri_state"))
    )
    (net (code "77") (name "unconnected-(C_U4-NC-Pad3)") (class "Default")
      (node (ref "C_U4") (pin "3") (pinfunction "NC_3") (pintype "tri_state"))
    )
    (net (code "78") (name "unconnected-(C_U4-NC-Pad4)") (class "Default")
      (node (ref "C_U4") (pin "4") (pinfunction "NC_4") (pintype "tri_state"))
    )
    (net (code "79") (name "unconnected-(C_U4-NC-Pad5)") (class "Default")
      (node (ref "C_U4") (pin "5") (pinfunction "NC_5") (pintype "tri_state"))
    )
    (net (code "80") (name "unconnected-(C_U4-NC-Pad14)") (class "Default")
      (node (ref "C_U4") (pin "14") (pinfunction "NC_14") (pintype "bidirectional"))
    )
    (net (code "81") (name "unconnected-(C_U4-NC-Pad15)") (class "Default")
      (node (ref "C_U4") (pin "15") (pinfunction "NC_15") (pintype "tri_state"))
    )
    (net (code "82") (name "unconnected-(C_U4-NC-Pad16)") (class "Default")
      (node (ref "C_U4") (pin "16") (pinfunction "NC_16") (pintype "tri_state"))
    )
    (net (code "83") (name "unconnected-(C_U4-NC-Pad17)") (class "Default")
      (node (ref "C_U4") (pin "17") (pinfunction "NC_17") (pintype "tri_state"))
    )
    (net (code "84") (name "unconnected-(C_U4-REGOUT-Pad10)") (class "Default")
      (node (ref "C_U4") (pin "10") (pinfunction "REGOUT_10") (pintype "passive"))
    )
    (net (code "85") (name "unconnected-(C_U4-RESV-Pad19)") (class "Default")
      (node (ref "C_U4") (pin "19") (pinfunction "RESV_19") (pintype "passive"))
    )
    (net (code "86") (name "unconnected-(C_U4-RESV-Pad21)") (class "Default")
      (node (ref "C_U4") (pin "21") (pinfunction "RESV_21") (pintype "passive"))
    )
  )
)
